# Firefly_Pendant.net
KiCad netlist of a schematic drawn in EAGLE
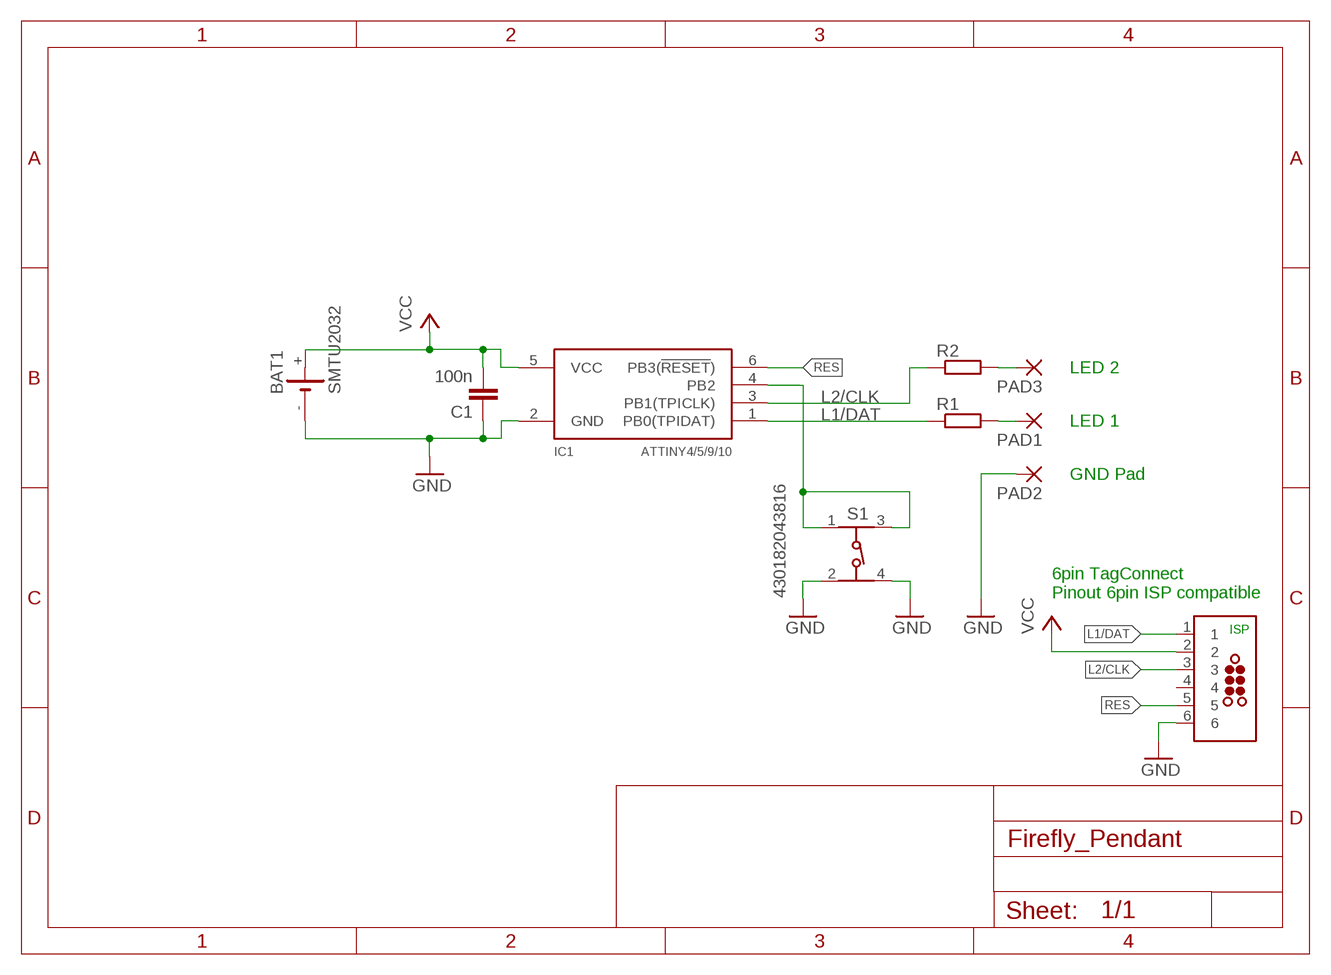
[diagram p0: schematic, sheet 1]

(export (version "E")
  (design (tool "Eeschema 10.0.6"))
  (components
    (comp (ref "BAT1")
      (value "SMTU2032")
      (footprint "eagle-import:SMTU2032")
      (libsource (lib "eagle-import") (part "SMTU2032"))
    )
    (comp (ref "C1")
      (value "100n")
      (footprint "eagle-import:C0603")
      (libsource (lib "eagle-import") (part "C-EUC0603"))
    )
    (comp (ref "IC1")
      (value "ATTINY4/5/9/10")
      (footprint "eagle-import:SOT23-6")
      (libsource (lib "eagle-import") (part "ATTINY4/5/9/10"))
    )
    (comp (ref "J1")
      (value "TAG-CONNECT_TC2030-MCP-NL")
      (footprint "eagle-import:TAG-CONNECT_TC2030-MCP-NL")
      (libsource (lib "eagle-import") (part "TAG-CONNECT_TC2030-MCP-NL"))
    )
    (comp (ref "PAD1")
      (value "WIREPADSMD1,27-254")
      (footprint "eagle-import:SMD1,27-2,54")
      (libsource (lib "eagle-import") (part "WIREPADSMD1,27-254"))
    )
    (comp (ref "PAD2")
      (value "WIREPADSMD1,27-254")
      (footprint "eagle-import:SMD1,27-2,54")
      (libsource (lib "eagle-import") (part "WIREPADSMD1,27-254"))
    )
    (comp (ref "PAD3")
      (value "WIREPADSMD1,27-254")
      (footprint "eagle-import:SMD1,27-2,54")
      (libsource (lib "eagle-import") (part "WIREPADSMD1,27-254"))
    )
    (comp (ref "R1")
      (value "R-EU_R0603")
      (footprint "eagle-import:R0603")
      (libsource (lib "eagle-import") (part "R-EU_R0603"))
    )
    (comp (ref "R2")
      (value "R-EU_R0603")
      (footprint "eagle-import:R0603")
      (libsource (lib "eagle-import") (part "R-EU_R0603"))
    )
    (comp (ref "S1")
      (value "430182043816")
      (footprint "eagle-import:430182043816")
      (libsource (lib "eagle-import") (part "430182043816"))
    )
  )
  (nets
    (net (code "1") (name "GND") (class "Default")
      (node (ref "BAT1") (pin "-") (pinfunction "-_-") (pintype "passive"))
      (node (ref "C1") (pin "1") (pinfunction "1_1") (pintype "passive"))
      (node (ref "IC1") (pin "2") (pinfunction "GND_2") (pintype "bidirectional"))
      (node (ref "J1") (pin "6") (pinfunction "6_6") (pintype "bidirectional"))
      (node (ref "PAD2") (pin "1") (pinfunction "P_1") (pintype "passive"))
      (node (ref "S1") (pin "2") (pinfunction "2_2") (pintype "passive"))
      (node (ref "S1") (pin "4") (pinfunction "4_4") (pintype "passive"))
    )
    (net (code "2") (name "L1{slash}DAT") (class "Default")
      (node (ref "IC1") (pin "1") (pinfunction "PB0(TPIDAT)_1") (pintype "bidirectional"))
      (node (ref "J1") (pin "1") (pinfunction "1_1") (pintype "passive"))
      (node (ref "R1") (pin "1") (pinfunction "1_1") (pintype "passive"))
    )
    (net (code "3") (name "L2{slash}CLK") (class "Default")
      (node (ref "IC1") (pin "3") (pinfunction "PB1(TPICLK)_3") (pintype "bidirectional"))
      (node (ref "J1") (pin "3") (pinfunction "3_3") (pintype "power_in"))
      (node (ref "R2") (pin "1") (pinfunction "1_1") (pintype "passive"))
    )
    (net (code "4") (name "Net-(IC1-PB2)") (class "Default")
      (node (ref "IC1") (pin "4") (pinfunction "PB2_4") (pintype "bidirectional"))
      (node (ref "S1") (pin "1") (pinfunction "1_1") (pintype "passive"))
      (node (ref "S1") (pin "3") (pinfunction "3_3") (pintype "passive"))
    )
    (net (code "5") (name "Net-(PAD1-P)") (class "Default")
      (node (ref "PAD1") (pin "1") (pinfunction "P_1") (pintype "passive"))
      (node (ref "R1") (pin "2") (pinfunction "2_2") (pintype "passive"))
    )
    (net (code "6") (name "Net-(PAD3-P)") (class "Default")
      (node (ref "PAD3") (pin "1") (pinfunction "P_1") (pintype "passive"))
      (node (ref "R2") (pin "2") (pinfunction "2_2") (pintype "passive"))
    )
    (net (code "7") (name "RES") (class "Default")
      (node (ref "IC1") (pin "6") (pinfunction "PB3(~{RESET})_6") (pintype "bidirectional"))
      (node (ref "J1") (pin "5") (pinfunction "5_5") (pintype "output"))
    )
    (net (code "8") (name "VCC") (class "Default")
      (node (ref "BAT1") (pin "+") (pinfunction "+_+") (pintype "passive"))
      (node (ref "C1") (pin "2") (pinfunction "2_2") (pintype "passive"))
      (node (ref "IC1") (pin "5") (pinfunction "VCC_5") (pintype "bidirectional"))
      (node (ref "J1") (pin "2") (pinfunction "2_2") (pintype "power_in"))
    )
    (net (code "9") (name "unconnected-(J1-Pad4)") (class "Default")
      (node (ref "J1") (pin "4") (pinfunction "4_4") (pintype "bidirectional"))
    )
  )
)
